# amp-PA-UHF-TQP7M9106.net
KiCad netlist of a schematic drawn in EAGLE
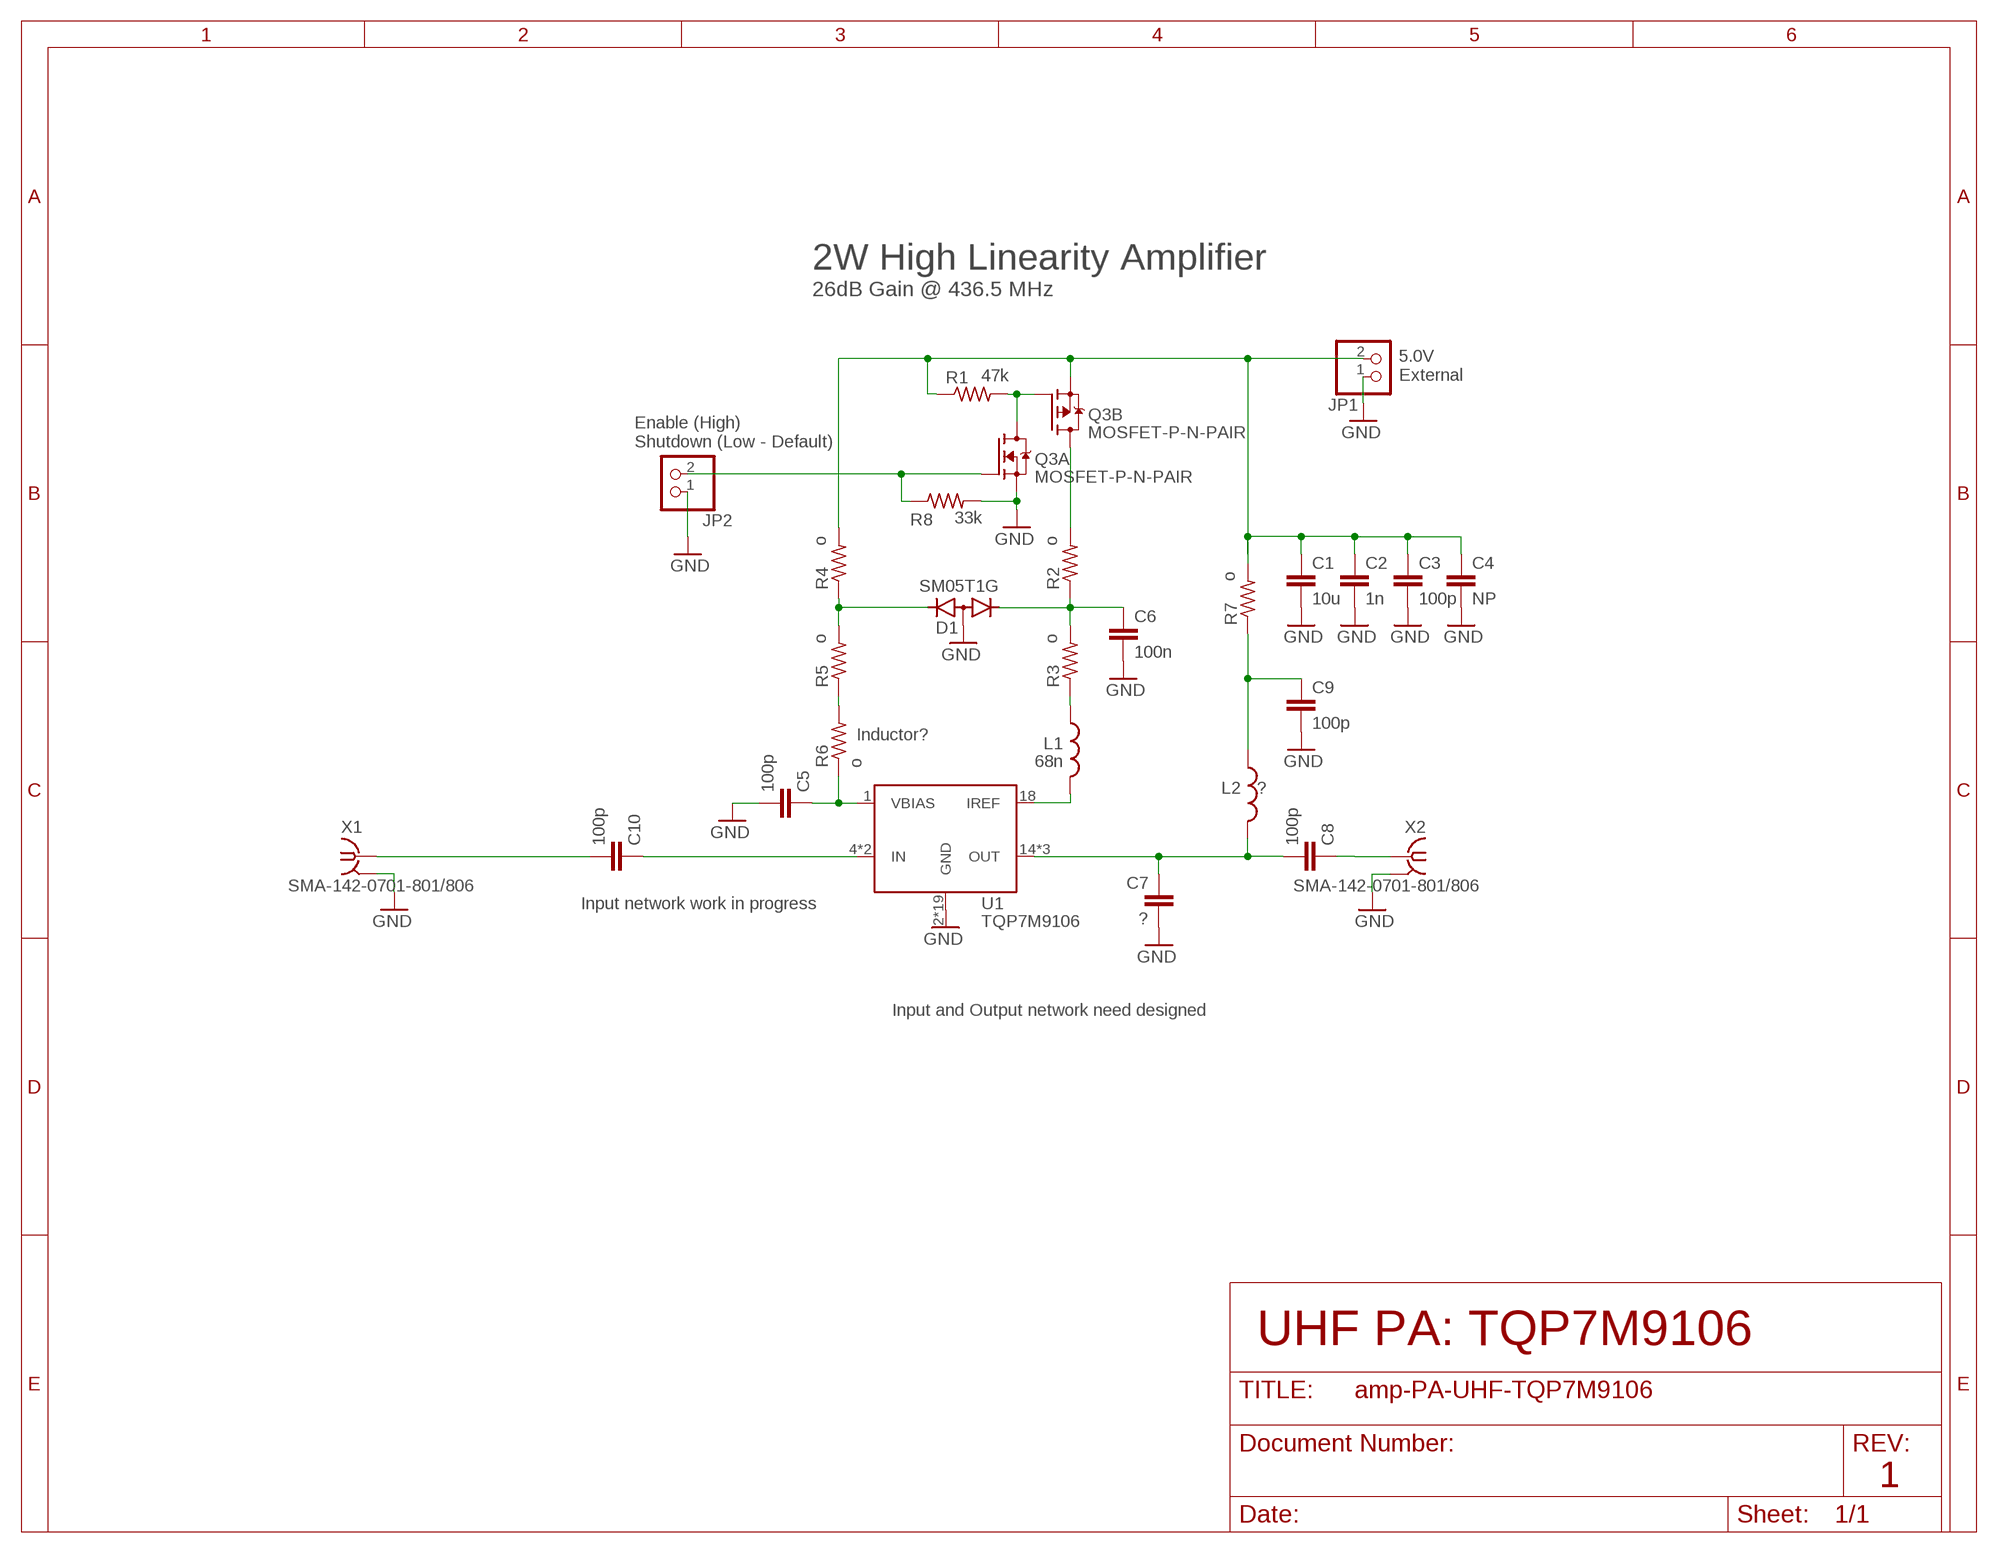
[diagram p0: schematic, sheet 1]

(export (version "E")
  (design (tool "Eeschema 10.0.6"))
  (components
    (comp (ref "C1")
      (value "10u")
      (footprint "eagle-import:.0603-B-NOSILK")
      (libsource (lib "eagle-import") (part "C-EU0603-B-NOSILK"))
    )
    (comp (ref "C2")
      (value "1n")
      (footprint "eagle-import:.0603-B-NOSILK")
      (libsource (lib "eagle-import") (part "C-EU0603-B-NOSILK"))
    )
    (comp (ref "C3")
      (value "100p")
      (footprint "eagle-import:.0603-B-NOSILK")
      (libsource (lib "eagle-import") (part "C-EU0603-B-NOSILK"))
    )
    (comp (ref "C4")
      (value "NP")
      (footprint "eagle-import:.0603-B-NOSILK")
      (libsource (lib "eagle-import") (part "C-EU0603-B-NOSILK"))
    )
    (comp (ref "C5")
      (value "100p")
      (footprint "eagle-import:.0603-B-NOSILK")
      (libsource (lib "eagle-import") (part "C-EU0603-B-NOSILK"))
    )
    (comp (ref "C6")
      (value "100n")
      (footprint "eagle-import:.0603-B-NOSILK")
      (libsource (lib "eagle-import") (part "C-EU0603-B-NOSILK"))
    )
    (comp (ref "C7")
      (value "?")
      (footprint "eagle-import:.0402-B-NOSILK")
      (libsource (lib "eagle-import") (part "C-EU0402-B-NOSILK"))
    )
    (comp (ref "C8")
      (value "100p")
      (footprint "eagle-import:.0402-B-NOSILK")
      (libsource (lib "eagle-import") (part "C-EU0402-B-NOSILK"))
    )
    (comp (ref "C9")
      (value "100p")
      (footprint "eagle-import:.0603-B-NOSILK")
      (libsource (lib "eagle-import") (part "C-EU0603-B-NOSILK"))
    )
    (comp (ref "C10")
      (value "100p")
      (footprint "eagle-import:.0402-B-NOSILK")
      (libsource (lib "eagle-import") (part "C-EU0402-B-NOSILK"))
    )
    (comp (ref "D1")
      (value "SM05T1G")
      (footprint "eagle-import:SOT23")
      (libsource (lib "eagle-import") (part "DIODE-2CA|ACSOT23"))
    )
    (comp (ref "JP1")
      (value "PINHD-1X2")
      (footprint "eagle-import:1X02")
      (libsource (lib "eagle-import") (part "PINHD-1X2"))
    )
    (comp (ref "JP2")
      (value "PINHD-1X2")
      (footprint "eagle-import:1X02")
      (libsource (lib "eagle-import") (part "PINHD-1X2"))
    )
    (comp (ref "L1")
      (value "68n")
      (footprint "eagle-import:.0603-B-NOSILK")
      (libsource (lib "eagle-import") (part "L-US0603-B-NOSILK"))
    )
    (comp (ref "L2")
      (value "?")
      (footprint "eagle-import:.0805-B-NOSILK")
      (libsource (lib "eagle-import") (part "L-US0805-B-NOSILK"))
    )
    (comp (ref "Q3")
      (value "MOSFET-P-N-PAIR")
      (footprint "eagle-import:SOT23-6")
      (libsource (lib "eagle-import") (part "MOSFET-P-N-PAIR"))
    )
    (comp (ref "R1")
      (value "47k")
      (footprint "eagle-import:.0402-B-NOSILK")
      (libsource (lib "eagle-import") (part "R-US_0402-B-NOSILK"))
    )
    (comp (ref "R2")
      (value "o")
      (footprint "eagle-import:.0805-B-NOSILK")
      (libsource (lib "eagle-import") (part "R-US_0805-B-NOSILK"))
    )
    (comp (ref "R3")
      (value "o")
      (footprint "eagle-import:.0603-B-NOSILK")
      (libsource (lib "eagle-import") (part "R-US_0603-B-NOSILK"))
    )
    (comp (ref "R4")
      (value "o")
      (footprint "eagle-import:.0805-B-NOSILK")
      (libsource (lib "eagle-import") (part "R-US_0805-B-NOSILK"))
    )
    (comp (ref "R5")
      (value "o")
      (footprint "eagle-import:.0603-B-NOSILK")
      (libsource (lib "eagle-import") (part "R-US_0603-B-NOSILK"))
    )
    (comp (ref "R6")
      (value "o")
      (footprint "eagle-import:.0603-B-NOSILK")
      (libsource (lib "eagle-import") (part "R-US_0603-B-NOSILK"))
    )
    (comp (ref "R7")
      (value "o")
      (footprint "eagle-import:.0805-B-NOSILK")
      (libsource (lib "eagle-import") (part "R-US_0805-B-NOSILK"))
    )
    (comp (ref "R8")
      (value "33k")
      (footprint "eagle-import:.0402-B-NOSILK")
      (libsource (lib "eagle-import") (part "R-US_0402-B-NOSILK"))
    )
    (comp (ref "U1")
      (value "TQP7M9106")
      (footprint "eagle-import:QFN24-4X4-WITH-PAD")
      (libsource (lib "eagle-import") (part "TQP7M9106"))
    )
    (comp (ref "X1")
      (value "SMA-142-0701-801/806")
      (footprint "eagle-import:J502-ND-142-0701-801_806")
      (fields (field (name "MF") "JOHNSON COMPONENTS") (field (name "MPN") "142-0701-801"))
      (libsource (lib "eagle-import") (part "SMA-142-0701-801/806"))
    )
    (comp (ref "X2")
      (value "SMA-142-0701-801/806")
      (footprint "eagle-import:J502-ND-142-0701-801_806")
      (fields (field (name "MF") "JOHNSON COMPONENTS") (field (name "MPN") "142-0701-801"))
      (libsource (lib "eagle-import") (part "SMA-142-0701-801/806"))
    )
  )
  (nets
    (net (code "1") (name "GND") (class "Default")
      (node (ref "C1") (pin "2") (pinfunction "2_2") (pintype "passive"))
      (node (ref "C2") (pin "2") (pinfunction "2_2") (pintype "passive"))
      (node (ref "C3") (pin "2") (pinfunction "2_2") (pintype "passive"))
      (node (ref "C4") (pin "2") (pinfunction "2_2") (pintype "passive"))
      (node (ref "C5") (pin "2") (pinfunction "2_2") (pintype "passive"))
      (node (ref "C6") (pin "2") (pinfunction "2_2") (pintype "passive"))
      (node (ref "C7") (pin "2") (pinfunction "2_2") (pintype "passive"))
      (node (ref "C9") (pin "2") (pinfunction "2_2") (pintype "passive"))
      (node (ref "D1") (pin "3") (pinfunction "A_3") (pintype "passive"))
      (node (ref "JP1") (pin "1") (pinfunction "1_1") (pintype "passive"))
      (node (ref "JP2") (pin "1") (pinfunction "1_1") (pintype "passive"))
      (node (ref "Q3") (pin "5") (pinfunction "S_5") (pintype "passive"))
      (node (ref "R8") (pin "2") (pinfunction "2_2") (pintype "passive"))
      (node (ref "U1") (pin "10") (pinfunction "GND_10") (pintype "power_in"))
      (node (ref "U1") (pin "11") (pinfunction "GND_11") (pintype "power_in"))
      (node (ref "U1") (pin "12") (pinfunction "GND_12") (pintype "power_in"))
      (node (ref "U1") (pin "13") (pinfunction "GND_13") (pintype "power_in"))
      (node (ref "U1") (pin "17") (pinfunction "GND_17") (pintype "power_in"))
      (node (ref "U1") (pin "19") (pinfunction "GND_19") (pintype "power_in"))
      (node (ref "U1") (pin "2") (pinfunction "GND_2") (pintype "power_in"))
      (node (ref "U1") (pin "20") (pinfunction "GND_20") (pintype "power_in"))
      (node (ref "U1") (pin "21") (pinfunction "GND_21") (pintype "power_in"))
      (node (ref "U1") (pin "22") (pinfunction "GND_22") (pintype "power_in"))
      (node (ref "U1") (pin "23") (pinfunction "GND_23") (pintype "power_in"))
      (node (ref "U1") (pin "24") (pinfunction "GND_24") (pintype "power_in"))
      (node (ref "U1") (pin "3") (pinfunction "GND_3") (pintype "power_in"))
      (node (ref "U1") (pin "6") (pinfunction "GND_6") (pintype "power_in"))
      (node (ref "U1") (pin "7") (pinfunction "GND_7") (pintype "power_in"))
      (node (ref "U1") (pin "8") (pinfunction "GND_8") (pintype "power_in"))
      (node (ref "U1") (pin "9") (pinfunction "GND_9") (pintype "power_in"))
      (node (ref "U1") (pin "BPAD") (pinfunction "GND_BPAD") (pintype "power_in"))
      (node (ref "U1") (pin "TPAD") (pinfunction "GND_TPAD") (pintype "power_in"))
      (node (ref "X1") (pin "G@1") (pinfunction "2_G@1") (pintype "passive"))
      (node (ref "X1") (pin "G@2") (pinfunction "2_G@2") (pintype "passive"))
      (node (ref "X1") (pin "G@3") (pinfunction "2_G@3") (pintype "passive"))
      (node (ref "X1") (pin "G@4") (pinfunction "2_G@4") (pintype "passive"))
      (node (ref "X2") (pin "G@1") (pinfunction "2_G@1") (pintype "passive"))
      (node (ref "X2") (pin "G@2") (pinfunction "2_G@2") (pintype "passive"))
      (node (ref "X2") (pin "G@3") (pinfunction "2_G@3") (pintype "passive"))
      (node (ref "X2") (pin "G@4") (pinfunction "2_G@4") (pintype "passive"))
    )
    (net (code "2") (name "Net-(C7-Pad1)") (class "Default")
      (node (ref "C7") (pin "1") (pinfunction "1_1") (pintype "passive"))
      (node (ref "C8") (pin "2") (pinfunction "2_2") (pintype "passive"))
      (node (ref "L2") (pin "2") (pinfunction "2_2") (pintype "passive"))
      (node (ref "U1") (pin "14") (pinfunction "OUT_14") (pintype "output"))
      (node (ref "U1") (pin "15") (pinfunction "OUT_15") (pintype "output"))
      (node (ref "U1") (pin "16") (pinfunction "OUT_16") (pintype "output"))
    )
    (net (code "3") (name "Net-(C8-Pad1)") (class "Default")
      (node (ref "C8") (pin "1") (pinfunction "1_1") (pintype "passive"))
      (node (ref "X2") (pin "1") (pinfunction "1_1") (pintype "passive"))
    )
    (net (code "4") (name "Net-(C9-Pad1)") (class "Default")
      (node (ref "C9") (pin "1") (pinfunction "1_1") (pintype "passive"))
      (node (ref "L2") (pin "1") (pinfunction "1_1") (pintype "passive"))
      (node (ref "R7") (pin "1") (pinfunction "1_1") (pintype "passive"))
    )
    (net (code "5") (name "Net-(C10-Pad1)") (class "Default")
      (node (ref "C10") (pin "1") (pinfunction "1_1") (pintype "passive"))
      (node (ref "U1") (pin "4") (pinfunction "IN_4") (pintype "input"))
      (node (ref "U1") (pin "5") (pinfunction "IN_5") (pintype "input"))
    )
    (net (code "6") (name "Net-(C10-Pad2)") (class "Default")
      (node (ref "C10") (pin "2") (pinfunction "2_2") (pintype "passive"))
      (node (ref "X1") (pin "1") (pinfunction "1_1") (pintype "passive"))
    )
    (net (code "7") (name "Net-(D1-K1)") (class "Default")
      (node (ref "C6") (pin "1") (pinfunction "1_1") (pintype "passive"))
      (node (ref "D1") (pin "1") (pinfunction "K1_1") (pintype "passive"))
      (node (ref "R2") (pin "1") (pinfunction "1_1") (pintype "passive"))
      (node (ref "R3") (pin "2") (pinfunction "2_2") (pintype "passive"))
    )
    (net (code "8") (name "Net-(D1-K2)") (class "Default")
      (node (ref "D1") (pin "2") (pinfunction "K2_2") (pintype "passive"))
      (node (ref "R4") (pin "1") (pinfunction "1_1") (pintype "passive"))
      (node (ref "R5") (pin "2") (pinfunction "2_2") (pintype "passive"))
    )
    (net (code "9") (name "Net-(L1-Pad1)") (class "Default")
      (node (ref "L1") (pin "1") (pinfunction "1_1") (pintype "passive"))
      (node (ref "R3") (pin "1") (pinfunction "1_1") (pintype "passive"))
    )
    (net (code "10") (name "Net-(Q3A-D)") (class "Default")
      (node (ref "Q3") (pin "3") (pinfunction "G_3") (pintype "passive"))
      (node (ref "Q3") (pin "6") (pinfunction "D_6") (pintype "passive"))
      (node (ref "R1") (pin "2") (pinfunction "2_2") (pintype "passive"))
    )
    (net (code "11") (name "Net-(Q3A-G)") (class "Default")
      (node (ref "JP2") (pin "2") (pinfunction "2_2") (pintype "passive"))
      (node (ref "Q3") (pin "1") (pinfunction "G_1") (pintype "passive"))
      (node (ref "R8") (pin "1") (pinfunction "1_1") (pintype "passive"))
    )
    (net (code "12") (name "Net-(Q3B-D)") (class "Default")
      (node (ref "Q3") (pin "4") (pinfunction "D_4") (pintype "passive"))
      (node (ref "R2") (pin "2") (pinfunction "2_2") (pintype "passive"))
    )
    (net (code "13") (name "Net-(Q3B-S)") (class "Default")
      (node (ref "C1") (pin "1") (pinfunction "1_1") (pintype "passive"))
      (node (ref "C2") (pin "1") (pinfunction "1_1") (pintype "passive"))
      (node (ref "C3") (pin "1") (pinfunction "1_1") (pintype "passive"))
      (node (ref "C4") (pin "1") (pinfunction "1_1") (pintype "passive"))
      (node (ref "JP1") (pin "2") (pinfunction "2_2") (pintype "passive"))
      (node (ref "Q3") (pin "2") (pinfunction "S_2") (pintype "passive"))
      (node (ref "R1") (pin "1") (pinfunction "1_1") (pintype "passive"))
      (node (ref "R4") (pin "2") (pinfunction "2_2") (pintype "passive"))
      (node (ref "R7") (pin "2") (pinfunction "2_2") (pintype "passive"))
    )
    (net (code "14") (name "Net-(R5-Pad1)") (class "Default")
      (node (ref "R5") (pin "1") (pinfunction "1_1") (pintype "passive"))
      (node (ref "R6") (pin "2") (pinfunction "2_2") (pintype "passive"))
    )
    (net (code "15") (name "Net-(U1-IREF)") (class "Default")
      (node (ref "L1") (pin "2") (pinfunction "2_2") (pintype "passive"))
      (node (ref "U1") (pin "18") (pinfunction "IREF_18") (pintype "power_in"))
    )
    (net (code "16") (name "Net-(U1-VBIAS)") (class "Default")
      (node (ref "C5") (pin "1") (pinfunction "1_1") (pintype "passive"))
      (node (ref "R6") (pin "1") (pinfunction "1_1") (pintype "passive"))
      (node (ref "U1") (pin "1") (pinfunction "VBIAS_1") (pintype "power_in"))
    )
  )
)
